# carousel.net
KiCad netlist of a schematic drawn in EAGLE
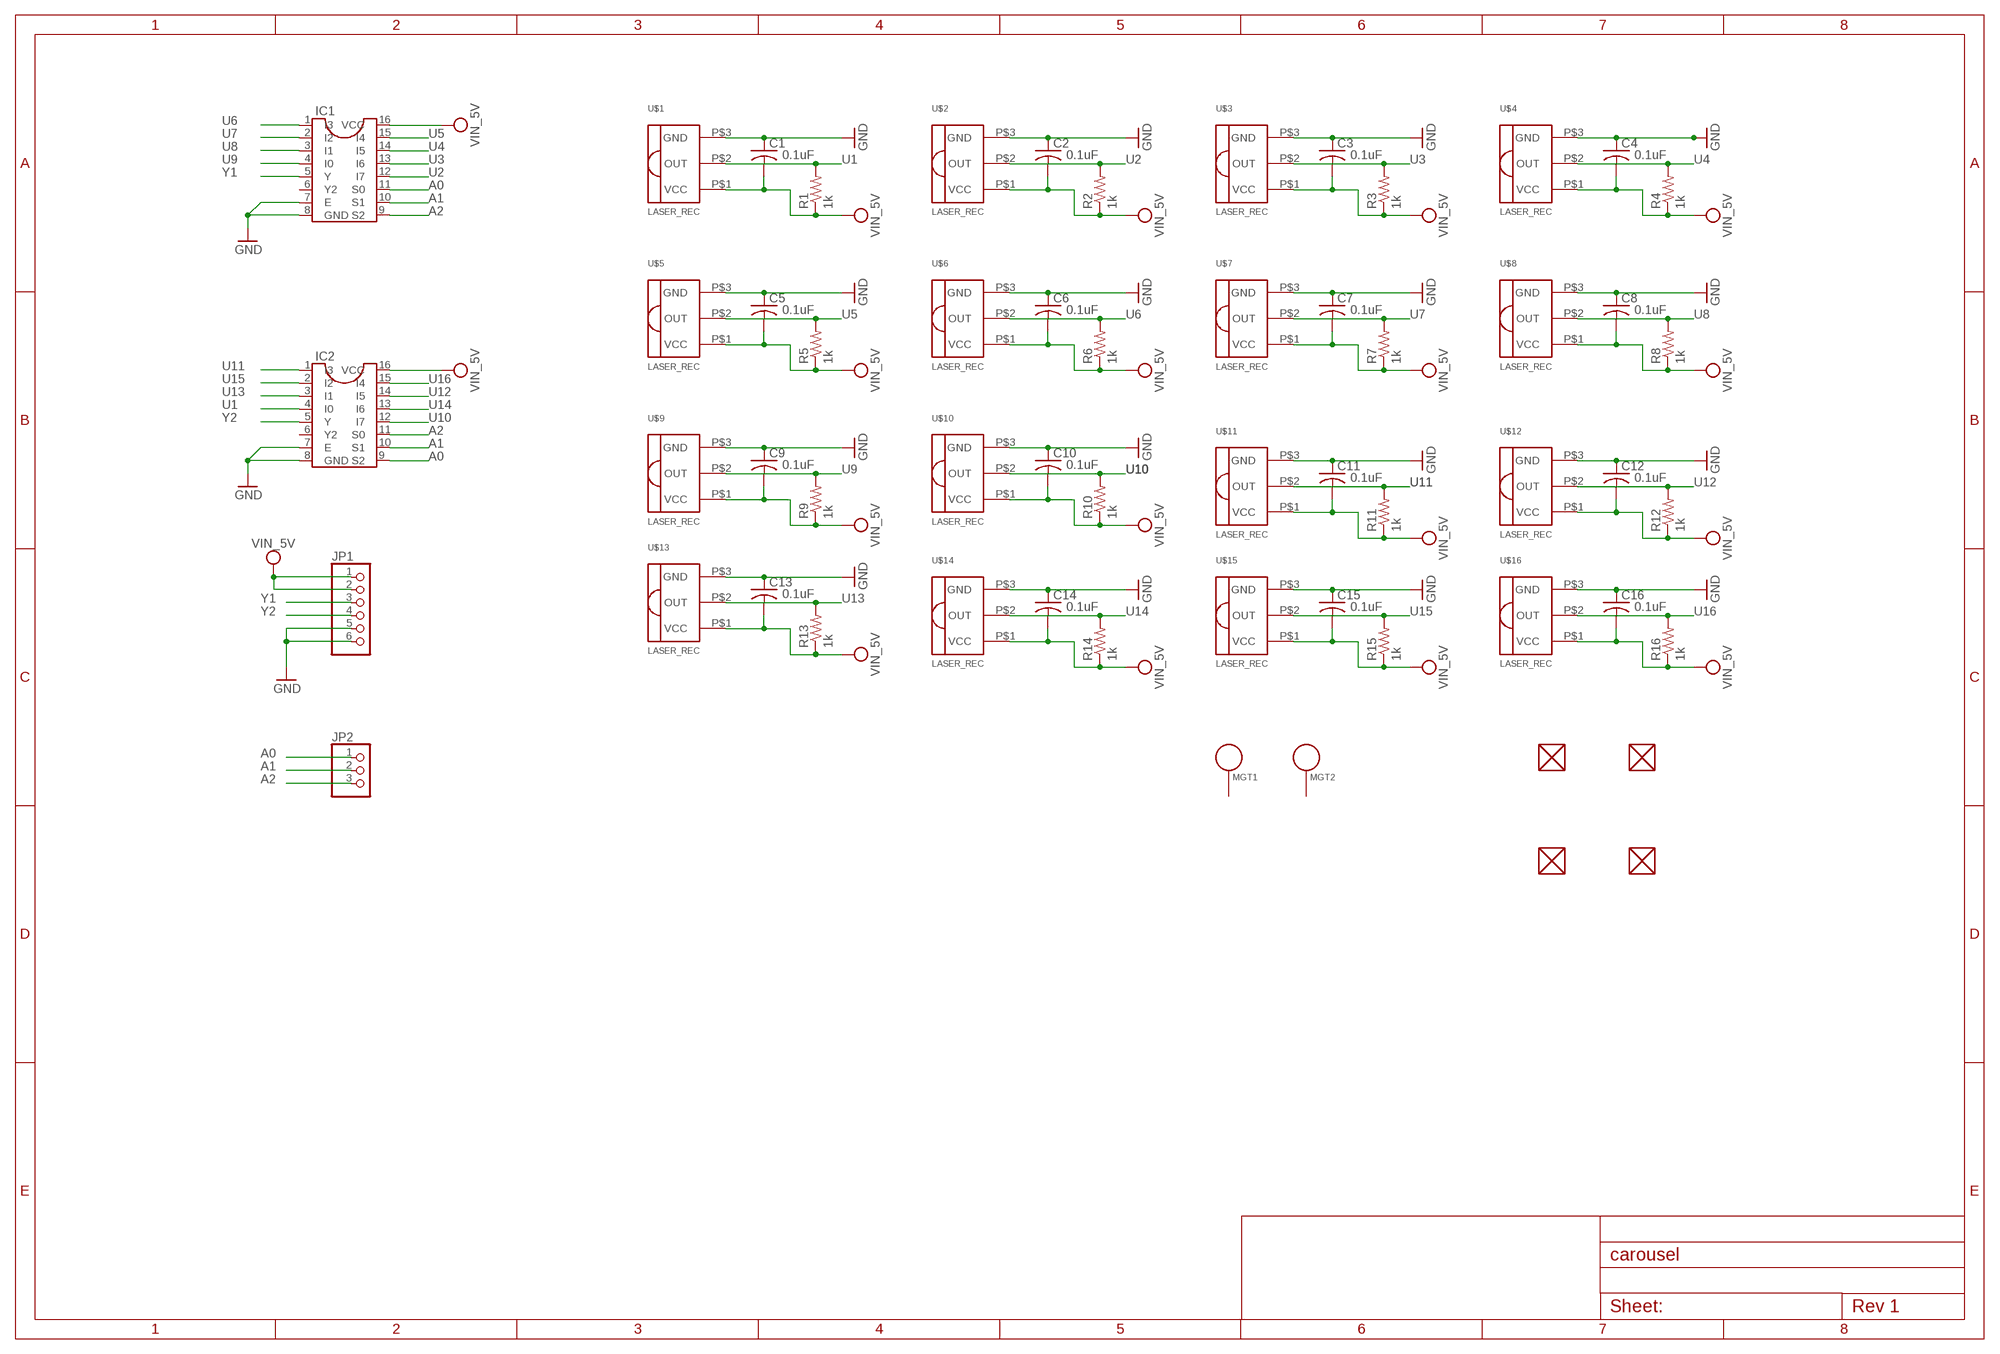
[diagram p0: schematic, sheet 1]

(export (version "E")
  (design (tool "Eeschema 10.0.6"))
  (components
    (comp (ref "C1")
      (value "0.1uF")
      (footprint "eagle-import:C025-024X044")
      (libsource (lib "eagle-import") (part "C-US025-024X044"))
    )
    (comp (ref "C2")
      (value "0.1uF")
      (footprint "eagle-import:C025-024X044")
      (libsource (lib "eagle-import") (part "C-US025-024X044"))
    )
    (comp (ref "C3")
      (value "0.1uF")
      (footprint "eagle-import:C025-024X044")
      (libsource (lib "eagle-import") (part "C-US025-024X044"))
    )
    (comp (ref "C4")
      (value "0.1uF")
      (footprint "eagle-import:C025-024X044")
      (libsource (lib "eagle-import") (part "C-US025-024X044"))
    )
    (comp (ref "C5")
      (value "0.1uF")
      (footprint "eagle-import:C025-024X044")
      (libsource (lib "eagle-import") (part "C-US025-024X044"))
    )
    (comp (ref "C6")
      (value "0.1uF")
      (footprint "eagle-import:C025-024X044")
      (libsource (lib "eagle-import") (part "C-US025-024X044"))
    )
    (comp (ref "C7")
      (value "0.1uF")
      (footprint "eagle-import:C025-024X044")
      (libsource (lib "eagle-import") (part "C-US025-024X044"))
    )
    (comp (ref "C8")
      (value "0.1uF")
      (footprint "eagle-import:C025-024X044")
      (libsource (lib "eagle-import") (part "C-US025-024X044"))
    )
    (comp (ref "C9")
      (value "0.1uF")
      (footprint "eagle-import:C025-024X044")
      (libsource (lib "eagle-import") (part "C-US025-024X044"))
    )
    (comp (ref "C10")
      (value "0.1uF")
      (footprint "eagle-import:C025-024X044")
      (libsource (lib "eagle-import") (part "C-US025-024X044"))
    )
    (comp (ref "C11")
      (value "0.1uF")
      (footprint "eagle-import:C025-024X044")
      (libsource (lib "eagle-import") (part "C-US025-024X044"))
    )
    (comp (ref "C12")
      (value "0.1uF")
      (footprint "eagle-import:C025-024X044")
      (libsource (lib "eagle-import") (part "C-US025-024X044"))
    )
    (comp (ref "C13")
      (value "0.1uF")
      (footprint "eagle-import:C025-024X044")
      (libsource (lib "eagle-import") (part "C-US025-024X044"))
    )
    (comp (ref "C14")
      (value "0.1uF")
      (footprint "eagle-import:C025-024X044")
      (libsource (lib "eagle-import") (part "C-US025-024X044"))
    )
    (comp (ref "C15")
      (value "0.1uF")
      (footprint "eagle-import:C025-024X044")
      (libsource (lib "eagle-import") (part "C-US025-024X044"))
    )
    (comp (ref "C16")
      (value "0.1uF")
      (footprint "eagle-import:C025-024X044")
      (libsource (lib "eagle-import") (part "C-US025-024X044"))
    )
    (comp (ref "FUD1")
      (value "FIDUCIAL")
      (footprint "eagle-import:FIDUCIAL_40MIL")
      (libsource (lib "eagle-import") (part "FIDUCIAL"))
    )
    (comp (ref "FUD2")
      (value "FIDUCIAL")
      (footprint "eagle-import:FIDUCIAL_40MIL")
      (libsource (lib "eagle-import") (part "FIDUCIAL"))
    )
    (comp (ref "FUD3")
      (value "FIDUCIAL")
      (footprint "eagle-import:FIDUCIAL_40MIL")
      (libsource (lib "eagle-import") (part "FIDUCIAL"))
    )
    (comp (ref "FUD4")
      (value "FIDUCIAL")
      (footprint "eagle-import:FIDUCIAL_40MIL")
      (libsource (lib "eagle-import") (part "FIDUCIAL"))
    )
    (comp (ref "IC1")
      (value "CD74HCT151S")
      (footprint "eagle-import:CD74HCT151")
      (libsource (lib "eagle-import") (part "CD74HCT151S"))
    )
    (comp (ref "IC2")
      (value "CD74HCT151S")
      (footprint "eagle-import:CD74HCT151")
      (libsource (lib "eagle-import") (part "CD74HCT151S"))
    )
    (comp (ref "JP1")
      (value "PINHD-1X6")
      (footprint "eagle-import:1X06")
      (libsource (lib "eagle-import") (part "PINHD-1X6"))
    )
    (comp (ref "JP2")
      (value "PINHD-1X3")
      (footprint "eagle-import:1X03")
      (libsource (lib "eagle-import") (part "PINHD-1X3"))
    )
    (comp (ref "MGT1")
      (value "MOUNTING_HOLE")
      (footprint "eagle-import:MOUNTING_HOLE")
      (libsource (lib "eagle-import") (part "MOUNTING_HOLE"))
    )
    (comp (ref "MGT2")
      (value "MOUNTING_HOLE")
      (footprint "eagle-import:MOUNTING_HOLE")
      (libsource (lib "eagle-import") (part "MOUNTING_HOLE"))
    )
    (comp (ref "R1")
      (value "1k")
      (footprint "eagle-import:0204V")
      (libsource (lib "eagle-import") (part "R-US_0204/2V"))
    )
    (comp (ref "R2")
      (value "1k")
      (footprint "eagle-import:0204V")
      (libsource (lib "eagle-import") (part "R-US_0204/2V"))
    )
    (comp (ref "R3")
      (value "1k")
      (footprint "eagle-import:0204V")
      (libsource (lib "eagle-import") (part "R-US_0204/2V"))
    )
    (comp (ref "R4")
      (value "1k")
      (footprint "eagle-import:0204V")
      (libsource (lib "eagle-import") (part "R-US_0204/2V"))
    )
    (comp (ref "R5")
      (value "1k")
      (footprint "eagle-import:0204V")
      (libsource (lib "eagle-import") (part "R-US_0204/2V"))
    )
    (comp (ref "R6")
      (value "1k")
      (footprint "eagle-import:0204V")
      (libsource (lib "eagle-import") (part "R-US_0204/2V"))
    )
    (comp (ref "R7")
      (value "1k")
      (footprint "eagle-import:0204V")
      (libsource (lib "eagle-import") (part "R-US_0204/2V"))
    )
    (comp (ref "R8")
      (value "1k")
      (footprint "eagle-import:0204V")
      (libsource (lib "eagle-import") (part "R-US_0204/2V"))
    )
    (comp (ref "R9")
      (value "1k")
      (footprint "eagle-import:0204V")
      (libsource (lib "eagle-import") (part "R-US_0204/2V"))
    )
    (comp (ref "R10")
      (value "1k")
      (footprint "eagle-import:0204V")
      (libsource (lib "eagle-import") (part "R-US_0204/2V"))
    )
    (comp (ref "R11")
      (value "1k")
      (footprint "eagle-import:0204V")
      (libsource (lib "eagle-import") (part "R-US_0204/2V"))
    )
    (comp (ref "R12")
      (value "1k")
      (footprint "eagle-import:0204V")
      (libsource (lib "eagle-import") (part "R-US_0204/2V"))
    )
    (comp (ref "R13")
      (value "1k")
      (footprint "eagle-import:0204V")
      (libsource (lib "eagle-import") (part "R-US_0204/2V"))
    )
    (comp (ref "R14")
      (value "1k")
      (footprint "eagle-import:0204V")
      (libsource (lib "eagle-import") (part "R-US_0204/2V"))
    )
    (comp (ref "R15")
      (value "1k")
      (footprint "eagle-import:0204V")
      (libsource (lib "eagle-import") (part "R-US_0204/2V"))
    )
    (comp (ref "R16")
      (value "1k")
      (footprint "eagle-import:0204V")
      (libsource (lib "eagle-import") (part "R-US_0204/2V"))
    )
    (comp (ref "U$1")
      (value "LASER_REC")
      (footprint "eagle-import:LSR_RC")
      (libsource (lib "eagle-import") (part "LASER_REC"))
    )
    (comp (ref "U$2")
      (value "LASER_REC")
      (footprint "eagle-import:LSR_RC")
      (libsource (lib "eagle-import") (part "LASER_REC"))
    )
    (comp (ref "U$3")
      (value "LASER_REC")
      (footprint "eagle-import:LSR_RC")
      (libsource (lib "eagle-import") (part "LASER_REC"))
    )
    (comp (ref "U$4")
      (value "LASER_REC")
      (footprint "eagle-import:LSR_RC")
      (libsource (lib "eagle-import") (part "LASER_REC"))
    )
    (comp (ref "U$5")
      (value "LASER_REC")
      (footprint "eagle-import:LSR_RC")
      (libsource (lib "eagle-import") (part "LASER_REC"))
    )
    (comp (ref "U$6")
      (value "LASER_REC")
      (footprint "eagle-import:LSR_RC")
      (libsource (lib "eagle-import") (part "LASER_REC"))
    )
    (comp (ref "U$7")
      (value "LASER_REC")
      (footprint "eagle-import:LSR_RC")
      (libsource (lib "eagle-import") (part "LASER_REC"))
    )
    (comp (ref "U$8")
      (value "LASER_REC")
      (footprint "eagle-import:LSR_RC")
      (libsource (lib "eagle-import") (part "LASER_REC"))
    )
    (comp (ref "U$9")
      (value "LASER_REC")
      (footprint "eagle-import:LSR_RC")
      (libsource (lib "eagle-import") (part "LASER_REC"))
    )
    (comp (ref "U$10")
      (value "LASER_REC")
      (footprint "eagle-import:LSR_RC")
      (libsource (lib "eagle-import") (part "LASER_REC"))
    )
    (comp (ref "U$11")
      (value "LASER_REC")
      (footprint "eagle-import:LSR_RC")
      (libsource (lib "eagle-import") (part "LASER_REC"))
    )
    (comp (ref "U$12")
      (value "LASER_REC")
      (footprint "eagle-import:LSR_RC")
      (libsource (lib "eagle-import") (part "LASER_REC"))
    )
    (comp (ref "U$13")
      (value "LASER_REC")
      (footprint "eagle-import:LSR_RC")
      (libsource (lib "eagle-import") (part "LASER_REC"))
    )
    (comp (ref "U$14")
      (value "LASER_REC")
      (footprint "eagle-import:LSR_RC")
      (libsource (lib "eagle-import") (part "LASER_REC"))
    )
    (comp (ref "U$15")
      (value "LASER_REC")
      (footprint "eagle-import:LSR_RC")
      (libsource (lib "eagle-import") (part "LASER_REC"))
    )
    (comp (ref "U$16")
      (value "LASER_REC")
      (footprint "eagle-import:LSR_RC")
      (libsource (lib "eagle-import") (part "LASER_REC"))
    )
  )
  (nets
    (net (code "1") (name "/A0") (class "Default")
      (node (ref "IC1") (pin "11") (pinfunction "S0_11") (pintype "input"))
      (node (ref "IC2") (pin "9") (pinfunction "S2_9") (pintype "input"))
      (node (ref "JP2") (pin "1") (pinfunction "1_1") (pintype "passive"))
    )
    (net (code "2") (name "/A1") (class "Default")
      (node (ref "IC1") (pin "10") (pinfunction "S1_10") (pintype "input"))
      (node (ref "IC2") (pin "10") (pinfunction "S1_10") (pintype "input"))
      (node (ref "JP2") (pin "2") (pinfunction "2_2") (pintype "passive"))
    )
    (net (code "3") (name "/A2") (class "Default")
      (node (ref "IC1") (pin "9") (pinfunction "S2_9") (pintype "input"))
      (node (ref "IC2") (pin "11") (pinfunction "S0_11") (pintype "input"))
      (node (ref "JP2") (pin "3") (pinfunction "3_3") (pintype "passive"))
    )
    (net (code "4") (name "/U1") (class "Default")
      (node (ref "IC2") (pin "4") (pinfunction "I0_4") (pintype "input"))
      (node (ref "R1") (pin "2") (pinfunction "2_2") (pintype "passive"))
      (node (ref "U$1") (pin "P$2") (pinfunction "OUT_P$2") (pintype "output"))
    )
    (net (code "5") (name "/U2") (class "Default")
      (node (ref "IC1") (pin "12") (pinfunction "I7_12") (pintype "input"))
      (node (ref "R2") (pin "2") (pinfunction "2_2") (pintype "passive"))
      (node (ref "U$2") (pin "P$2") (pinfunction "OUT_P$2") (pintype "output"))
    )
    (net (code "6") (name "/U3") (class "Default")
      (node (ref "IC1") (pin "13") (pinfunction "I6_13") (pintype "input"))
      (node (ref "R3") (pin "2") (pinfunction "2_2") (pintype "passive"))
      (node (ref "U$3") (pin "P$2") (pinfunction "OUT_P$2") (pintype "output"))
    )
    (net (code "7") (name "/U4") (class "Default")
      (node (ref "IC1") (pin "14") (pinfunction "I5_14") (pintype "input"))
      (node (ref "R4") (pin "2") (pinfunction "2_2") (pintype "passive"))
      (node (ref "U$4") (pin "P$2") (pinfunction "OUT_P$2") (pintype "output"))
    )
    (net (code "8") (name "/U5") (class "Default")
      (node (ref "IC1") (pin "15") (pinfunction "I4_15") (pintype "input"))
      (node (ref "R5") (pin "2") (pinfunction "2_2") (pintype "passive"))
      (node (ref "U$5") (pin "P$2") (pinfunction "OUT_P$2") (pintype "output"))
    )
    (net (code "9") (name "/U6") (class "Default")
      (node (ref "IC1") (pin "1") (pinfunction "I3_1") (pintype "input"))
      (node (ref "R6") (pin "2") (pinfunction "2_2") (pintype "passive"))
      (node (ref "U$6") (pin "P$2") (pinfunction "OUT_P$2") (pintype "output"))
    )
    (net (code "10") (name "/U7") (class "Default")
      (node (ref "IC1") (pin "2") (pinfunction "I2_2") (pintype "input"))
      (node (ref "R7") (pin "2") (pinfunction "2_2") (pintype "passive"))
      (node (ref "U$7") (pin "P$2") (pinfunction "OUT_P$2") (pintype "output"))
    )
    (net (code "11") (name "/U8") (class "Default")
      (node (ref "IC1") (pin "3") (pinfunction "I1_3") (pintype "input"))
      (node (ref "R8") (pin "2") (pinfunction "2_2") (pintype "passive"))
      (node (ref "U$8") (pin "P$2") (pinfunction "OUT_P$2") (pintype "output"))
    )
    (net (code "12") (name "/U9") (class "Default")
      (node (ref "IC1") (pin "4") (pinfunction "I0_4") (pintype "input"))
      (node (ref "R9") (pin "2") (pinfunction "2_2") (pintype "passive"))
      (node (ref "U$9") (pin "P$2") (pinfunction "OUT_P$2") (pintype "output"))
    )
    (net (code "13") (name "/U10") (class "Default")
      (node (ref "IC2") (pin "12") (pinfunction "I7_12") (pintype "input"))
      (node (ref "R10") (pin "2") (pinfunction "2_2") (pintype "passive"))
      (node (ref "U$10") (pin "P$2") (pinfunction "OUT_P$2") (pintype "output"))
    )
    (net (code "14") (name "/U11") (class "Default")
      (node (ref "IC2") (pin "1") (pinfunction "I3_1") (pintype "input"))
      (node (ref "R11") (pin "2") (pinfunction "2_2") (pintype "passive"))
      (node (ref "U$11") (pin "P$2") (pinfunction "OUT_P$2") (pintype "output"))
    )
    (net (code "15") (name "/U12") (class "Default")
      (node (ref "IC2") (pin "14") (pinfunction "I5_14") (pintype "input"))
      (node (ref "R12") (pin "2") (pinfunction "2_2") (pintype "passive"))
      (node (ref "U$12") (pin "P$2") (pinfunction "OUT_P$2") (pintype "output"))
    )
    (net (code "16") (name "/U13") (class "Default")
      (node (ref "IC2") (pin "3") (pinfunction "I1_3") (pintype "input"))
      (node (ref "R13") (pin "2") (pinfunction "2_2") (pintype "passive"))
      (node (ref "U$13") (pin "P$2") (pinfunction "OUT_P$2") (pintype "output"))
    )
    (net (code "17") (name "/U14") (class "Default")
      (node (ref "IC2") (pin "13") (pinfunction "I6_13") (pintype "input"))
      (node (ref "R14") (pin "2") (pinfunction "2_2") (pintype "passive"))
      (node (ref "U$14") (pin "P$2") (pinfunction "OUT_P$2") (pintype "output"))
    )
    (net (code "18") (name "/U15") (class "Default")
      (node (ref "IC2") (pin "2") (pinfunction "I2_2") (pintype "input"))
      (node (ref "R15") (pin "2") (pinfunction "2_2") (pintype "passive"))
      (node (ref "U$15") (pin "P$2") (pinfunction "OUT_P$2") (pintype "output"))
    )
    (net (code "19") (name "/U16") (class "Default")
      (node (ref "IC2") (pin "15") (pinfunction "I4_15") (pintype "input"))
      (node (ref "R16") (pin "2") (pinfunction "2_2") (pintype "passive"))
      (node (ref "U$16") (pin "P$2") (pinfunction "OUT_P$2") (pintype "output"))
    )
    (net (code "20") (name "/Y1") (class "Default")
      (node (ref "IC1") (pin "5") (pinfunction "Y_5") (pintype "output"))
      (node (ref "JP1") (pin "3") (pinfunction "3_3") (pintype "passive"))
    )
    (net (code "21") (name "/Y2") (class "Default")
      (node (ref "IC2") (pin "5") (pinfunction "Y_5") (pintype "output"))
      (node (ref "JP1") (pin "4") (pinfunction "4_4") (pintype "passive"))
    )
    (net (code "22") (name "GND") (class "Default")
      (node (ref "C1") (pin "1") (pinfunction "1_1") (pintype "passive"))
      (node (ref "C10") (pin "1") (pinfunction "1_1") (pintype "passive"))
      (node (ref "C11") (pin "1") (pinfunction "1_1") (pintype "passive"))
      (node (ref "C12") (pin "1") (pinfunction "1_1") (pintype "passive"))
      (node (ref "C13") (pin "1") (pinfunction "1_1") (pintype "passive"))
      (node (ref "C14") (pin "1") (pinfunction "1_1") (pintype "passive"))
      (node (ref "C15") (pin "1") (pinfunction "1_1") (pintype "passive"))
      (node (ref "C16") (pin "1") (pinfunction "1_1") (pintype "passive"))
      (node (ref "C2") (pin "1") (pinfunction "1_1") (pintype "passive"))
      (node (ref "C3") (pin "1") (pinfunction "1_1") (pintype "passive"))
      (node (ref "C4") (pin "1") (pinfunction "1_1") (pintype "passive"))
      (node (ref "C5") (pin "1") (pinfunction "1_1") (pintype "passive"))
      (node (ref "C6") (pin "1") (pinfunction "1_1") (pintype "passive"))
      (node (ref "C7") (pin "1") (pinfunction "1_1") (pintype "passive"))
      (node (ref "C8") (pin "1") (pinfunction "1_1") (pintype "passive"))
      (node (ref "C9") (pin "1") (pinfunction "1_1") (pintype "passive"))
      (node (ref "IC1") (pin "7") (pinfunction "E_7") (pintype "power_in"))
      (node (ref "IC1") (pin "8") (pinfunction "GND_8") (pintype "power_in"))
      (node (ref "IC2") (pin "7") (pinfunction "E_7") (pintype "power_in"))
      (node (ref "IC2") (pin "8") (pinfunction "GND_8") (pintype "power_in"))
      (node (ref "JP1") (pin "5") (pinfunction "5_5") (pintype "passive"))
      (node (ref "JP1") (pin "6") (pinfunction "6_6") (pintype "passive"))
      (node (ref "U$1") (pin "P$3") (pinfunction "GND_P$3") (pintype "power_in"))
      (node (ref "U$10") (pin "P$3") (pinfunction "GND_P$3") (pintype "power_in"))
      (node (ref "U$11") (pin "P$3") (pinfunction "GND_P$3") (pintype "power_in"))
      (node (ref "U$12") (pin "P$3") (pinfunction "GND_P$3") (pintype "power_in"))
      (node (ref "U$13") (pin "P$3") (pinfunction "GND_P$3") (pintype "power_in"))
      (node (ref "U$14") (pin "P$3") (pinfunction "GND_P$3") (pintype "power_in"))
      (node (ref "U$15") (pin "P$3") (pinfunction "GND_P$3") (pintype "power_in"))
      (node (ref "U$16") (pin "P$3") (pinfunction "GND_P$3") (pintype "power_in"))
      (node (ref "U$2") (pin "P$3") (pinfunction "GND_P$3") (pintype "power_in"))
      (node (ref "U$3") (pin "P$3") (pinfunction "GND_P$3") (pintype "power_in"))
      (node (ref "U$4") (pin "P$3") (pinfunction "GND_P$3") (pintype "power_in"))
      (node (ref "U$5") (pin "P$3") (pinfunction "GND_P$3") (pintype "power_in"))
      (node (ref "U$6") (pin "P$3") (pinfunction "GND_P$3") (pintype "power_in"))
      (node (ref "U$7") (pin "P$3") (pinfunction "GND_P$3") (pintype "power_in"))
      (node (ref "U$8") (pin "P$3") (pinfunction "GND_P$3") (pintype "power_in"))
      (node (ref "U$9") (pin "P$3") (pinfunction "GND_P$3") (pintype "power_in"))
    )
    (net (code "23") (name "VIN_5V") (class "Default")
      (node (ref "C1") (pin "2") (pinfunction "2_2") (pintype "passive"))
      (node (ref "C10") (pin "2") (pinfunction "2_2") (pintype "passive"))
      (node (ref "C11") (pin "2") (pinfunction "2_2") (pintype "passive"))
      (node (ref "C12") (pin "2") (pinfunction "2_2") (pintype "passive"))
      (node (ref "C13") (pin "2") (pinfunction "2_2") (pintype "passive"))
      (node (ref "C14") (pin "2") (pinfunction "2_2") (pintype "passive"))
      (node (ref "C15") (pin "2") (pinfunction "2_2") (pintype "passive"))
      (node (ref "C16") (pin "2") (pinfunction "2_2") (pintype "passive"))
      (node (ref "C2") (pin "2") (pinfunction "2_2") (pintype "passive"))
      (node (ref "C3") (pin "2") (pinfunction "2_2") (pintype "passive"))
      (node (ref "C4") (pin "2") (pinfunction "2_2") (pintype "passive"))
      (node (ref "C5") (pin "2") (pinfunction "2_2") (pintype "passive"))
      (node (ref "C6") (pin "2") (pinfunction "2_2") (pintype "passive"))
      (node (ref "C7") (pin "2") (pinfunction "2_2") (pintype "passive"))
      (node (ref "C8") (pin "2") (pinfunction "2_2") (pintype "passive"))
      (node (ref "C9") (pin "2") (pinfunction "2_2") (pintype "passive"))
      (node (ref "IC1") (pin "16") (pinfunction "VCC_16") (pintype "power_in"))
      (node (ref "IC2") (pin "16") (pinfunction "VCC_16") (pintype "power_in"))
      (node (ref "JP1") (pin "1") (pinfunction "1_1") (pintype "passive"))
      (node (ref "JP1") (pin "2") (pinfunction "2_2") (pintype "passive"))
      (node (ref "R1") (pin "1") (pinfunction "1_1") (pintype "passive"))
      (node (ref "R10") (pin "1") (pinfunction "1_1") (pintype "passive"))
      (node (ref "R11") (pin "1") (pinfunction "1_1") (pintype "passive"))
      (node (ref "R12") (pin "1") (pinfunction "1_1") (pintype "passive"))
      (node (ref "R13") (pin "1") (pinfunction "1_1") (pintype "passive"))
      (node (ref "R14") (pin "1") (pinfunction "1_1") (pintype "passive"))
      (node (ref "R15") (pin "1") (pinfunction "1_1") (pintype "passive"))
      (node (ref "R16") (pin "1") (pinfunction "1_1") (pintype "passive"))
      (node (ref "R2") (pin "1") (pinfunction "1_1") (pintype "passive"))
      (node (ref "R3") (pin "1") (pinfunction "1_1") (pintype "passive"))
      (node (ref "R4") (pin "1") (pinfunction "1_1") (pintype "passive"))
      (node (ref "R5") (pin "1") (pinfunction "1_1") (pintype "passive"))
      (node (ref "R6") (pin "1") (pinfunction "1_1") (pintype "passive"))
      (node (ref "R7") (pin "1") (pinfunction "1_1") (pintype "passive"))
      (node (ref "R8") (pin "1") (pinfunction "1_1") (pintype "passive"))
      (node (ref "R9") (pin "1") (pinfunction "1_1") (pintype "passive"))
      (node (ref "U$1") (pin "P$1") (pinfunction "VCC_P$1") (pintype "power_in"))
      (node (ref "U$10") (pin "P$1") (pinfunction "VCC_P$1") (pintype "power_in"))
      (node (ref "U$11") (pin "P$1") (pinfunction "VCC_P$1") (pintype "power_in"))
      (node (ref "U$12") (pin "P$1") (pinfunction "VCC_P$1") (pintype "power_in"))
      (node (ref "U$13") (pin "P$1") (pinfunction "VCC_P$1") (pintype "power_in"))
      (node (ref "U$14") (pin "P$1") (pinfunction "VCC_P$1") (pintype "power_in"))
      (node (ref "U$15") (pin "P$1") (pinfunction "VCC_P$1") (pintype "power_in"))
      (node (ref "U$16") (pin "P$1") (pinfunction "VCC_P$1") (pintype "power_in"))
      (node (ref "U$2") (pin "P$1") (pinfunction "VCC_P$1") (pintype "power_in"))
      (node (ref "U$3") (pin "P$1") (pinfunction "VCC_P$1") (pintype "power_in"))
      (node (ref "U$4") (pin "P$1") (pinfunction "VCC_P$1") (pintype "power_in"))
      (node (ref "U$5") (pin "P$1") (pinfunction "VCC_P$1") (pintype "power_in"))
      (node (ref "U$6") (pin "P$1") (pinfunction "VCC_P$1") (pintype "power_in"))
      (node (ref "U$7") (pin "P$1") (pinfunction "VCC_P$1") (pintype "power_in"))
      (node (ref "U$8") (pin "P$1") (pinfunction "VCC_P$1") (pintype "power_in"))
      (node (ref "U$9") (pin "P$1") (pinfunction "VCC_P$1") (pintype "power_in"))
    )
    (net (code "24") (name "unconnected-(FUD1-PadP$1)") (class "Default")
      (node (ref "FUD1") (pin "P$1") (pinfunction "P$1_P$1") (pintype "no_connect"))
    )
    (net (code "25") (name "unconnected-(FUD2-PadP$1)") (class "Default")
      (node (ref "FUD2") (pin "P$1") (pinfunction "P$1_P$1") (pintype "no_connect"))
    )
    (net (code "26") (name "unconnected-(FUD3-PadP$1)") (class "Default")
      (node (ref "FUD3") (pin "P$1") (pinfunction "P$1_P$1") (pintype "no_connect"))
    )
    (net (code "27") (name "unconnected-(FUD4-PadP$1)") (class "Default")
      (node (ref "FUD4") (pin "P$1") (pinfunction "P$1_P$1") (pintype "no_connect"))
    )
    (net (code "28") (name "unconnected-(IC1-Y2-Pad6)") (class "Default")
      (node (ref "IC1") (pin "6") (pinfunction "Y2_6") (pintype "output"))
    )
    (net (code "29") (name "unconnected-(IC2-Y2-Pad6)") (class "Default")
      (node (ref "IC2") (pin "6") (pinfunction "Y2_6") (pintype "output"))
    )
    (net (code "30") (name "unconnected-(MGT1-PadP$1)") (class "Default")
      (node (ref "MGT1") (pin "P$1") (pinfunction "P$1_P$1") (pintype "bidirectional"))
    )
    (net (code "31") (name "unconnected-(MGT2-PadP$1)") (class "Default")
      (node (ref "MGT2") (pin "P$1") (pinfunction "P$1_P$1") (pintype "bidirectional"))
    )
  )
)
